# HI8596PSI.net
KiCad netlist of a schematic drawn in Altium Designer
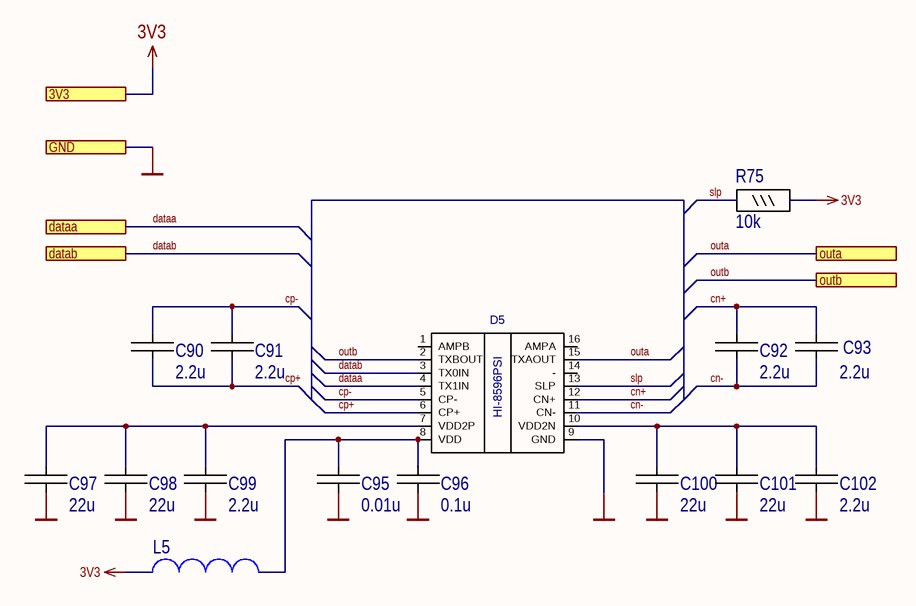
[diagram p0: HI8596PSI.SchDoc]

(export (version "E")
  (design (tool "Eeschema 10.0.6"))
  (components
    (comp (ref "C90")
      (value "2.2u")
      (footprint "C0603_IPC")
      (description "2.2µF ±10% 10V Ceramic Capacitor X7R 0603 (1608 Metric)")
      (fields (field (name "MPN") "CL10B225KP8NNNC") (field (name "TOLERANCE") "0,1"))
      (libsource (lib "DB_res_cap_ind") (part "C0603_GOST"))
    )
    (comp (ref "C91")
      (value "2.2u")
      (footprint "C0603_IPC")
      (description "2.2µF ±10% 10V Ceramic Capacitor X7R 0603 (1608 Metric)")
      (fields (field (name "MPN") "CL10B225KP8NNNC") (field (name "TOLERANCE") "0,1"))
      (libsource (lib "DB_res_cap_ind") (part "C0603_GOST"))
    )
    (comp (ref "C92")
      (value "2.2u")
      (footprint "C0603_IPC")
      (description "2.2µF ±10% 10V Ceramic Capacitor X7R 0603 (1608 Metric)")
      (fields (field (name "MPN") "CL10B225KP8NNNC") (field (name "TOLERANCE") "0,1"))
      (libsource (lib "DB_res_cap_ind") (part "C0603_GOST"))
    )
    (comp (ref "C93")
      (value "2.2u")
      (footprint "C0603_IPC")
      (description "2.2µF ±10% 10V Ceramic Capacitor X7R 0603 (1608 Metric)")
      (fields (field (name "MPN") "CL10B225KP8NNNC") (field (name "TOLERANCE") "0,1"))
      (libsource (lib "DB_res_cap_ind") (part "C0603_GOST"))
    )
    (comp (ref "C95")
      (value "0.01u")
      (footprint "C0603_IPC")
      (description "0.01uF ±10% 50V Ceramic Capacitor X7R 0603 (1608 Metric)")
      (fields (field (name "MPN") "CC0603KRX7R9BB103") (field (name "TOLERANCE") "0,1"))
      (libsource (lib "DB_res_cap_ind") (part "C0603_GOST"))
    )
    (comp (ref "C96")
      (value "0.1u")
      (footprint "C0603_IPC")
      (description "0.1uF ±10% 50V Ceramic Capacitor X7R 0603 (1608 Metric)")
      (fields (field (name "MPN") "CL10B104KB8NNND") (field (name "TOLERANCE") "0,1"))
      (libsource (lib "DB_res_cap_ind") (part "C0603_GOST"))
    )
    (comp (ref "C97")
      (value "22u")
      (footprint "C1206_IPC")
      (description "10µF ±10% 50V Ceramic Capacitor X5R 1206 (3216 Metric)")
      (fields
        (field (name "TOLERANCE") "0,2")
        (field (name "MANUFACTURER") "Murata Electronics North America")
      )
      (libsource (lib "DB_res_cap_ind") (part "C0603_GOST"))
    )
    (comp (ref "C98")
      (value "22u")
      (footprint "C1206_IPC")
      (description "10µF ±10% 50V Ceramic Capacitor X5R 1206 (3216 Metric)")
      (fields
        (field (name "TOLERANCE") "0,2")
        (field (name "MANUFACTURER") "Murata Electronics North America")
      )
      (libsource (lib "DB_res_cap_ind") (part "C0603_GOST"))
    )
    (comp (ref "C99")
      (value "2.2u")
      (footprint "C0603_IPC")
      (description "2.2µF ±10% 10V Ceramic Capacitor X7R 0603 (1608 Metric)")
      (fields (field (name "MPN") "CL10B225KP8NNNC") (field (name "TOLERANCE") "0,1"))
      (libsource (lib "DB_res_cap_ind") (part "C0603_GOST"))
    )
    (comp (ref "C100")
      (value "22u")
      (footprint "C1206_IPC")
      (description "10µF ±10% 50V Ceramic Capacitor X5R 1206 (3216 Metric)")
      (fields
        (field (name "TOLERANCE") "0,2")
        (field (name "MANUFACTURER") "Murata Electronics North America")
      )
      (libsource (lib "DB_res_cap_ind") (part "C0603_GOST"))
    )
    (comp (ref "C101")
      (value "22u")
      (footprint "C1206_IPC")
      (description "10µF ±10% 50V Ceramic Capacitor X5R 1206 (3216 Metric)")
      (fields
        (field (name "TOLERANCE") "0,2")
        (field (name "MANUFACTURER") "Murata Electronics North America")
      )
      (libsource (lib "DB_res_cap_ind") (part "C0603_GOST"))
    )
    (comp (ref "C102")
      (value "2.2u")
      (footprint "C0603_IPC")
      (description "2.2µF ±10% 10V Ceramic Capacitor X7R 0603 (1608 Metric)")
      (fields (field (name "MPN") "CL10B225KP8NNNC") (field (name "TOLERANCE") "0,1"))
      (libsource (lib "DB_res_cap_ind") (part "C0603_GOST"))
    )
    (comp (ref "D5")
      (value "HI-8596PSI")
      (footprint "soic16")
      (libsource (lib "EVAL_22_0B_rev_4_v2") (part "HI-8596PSI"))
    )
    (comp (ref "L5")
      (value "BLM21AG102SN1")
      (footprint "ind0805")
      (description "1 kOhms @ 100MHz 1 Ferrite Bead 0805 (2012 Metric) 500mA 280 mOhm")
      (fields
        (field (name "TOLERANCE") "±25%")
        (field (name "MANUFACTURER") "Murata Electronics North America")
      )
      (libsource (lib "DB_res_cap_ind") (part "INDUCTOR"))
    )
    (comp (ref "R75")
      (value "10k")
      (footprint "R0603")
      (description "10 kOhms ±5% 0.1W, 1/10W Chip Resistor 0603 (1608 Metric) Moisture Resistant Thick Film")
      (fields (field (name "MPN") "RC0603JR-0710kL") (field (name "TOLERANCE") "5%"))
      (libsource (lib "DB_res_cap_ind") (part "R0603"))
    )
  )
  (nets
    (net (code "1") (name "/cn+") (class "Default")
      (node (ref "C92") (pin "1") (pinfunction "1_1") (pintype "passive"))
      (node (ref "C93") (pin "1") (pinfunction "1_1") (pintype "passive"))
      (node (ref "D5") (pin "12") (pinfunction "CN+_12") (pintype "passive"))
    )
    (net (code "2") (name "/cn-") (class "Default")
      (node (ref "C92") (pin "2") (pinfunction "2_2") (pintype "passive"))
      (node (ref "C93") (pin "2") (pinfunction "2_2") (pintype "passive"))
      (node (ref "D5") (pin "11") (pinfunction "CN-_11") (pintype "passive"))
    )
    (net (code "3") (name "/cp+") (class "Default")
      (node (ref "C90") (pin "2") (pinfunction "2_2") (pintype "passive"))
      (node (ref "C91") (pin "2") (pinfunction "2_2") (pintype "passive"))
      (node (ref "D5") (pin "6") (pinfunction "CP+_6") (pintype "passive"))
    )
    (net (code "4") (name "/cp-") (class "Default")
      (node (ref "C90") (pin "1") (pinfunction "1_1") (pintype "passive"))
      (node (ref "C91") (pin "1") (pinfunction "1_1") (pintype "passive"))
      (node (ref "D5") (pin "5") (pinfunction "CP-_5") (pintype "passive"))
    )
    (net (code "5") (name "/dataa") (class "Default")
      (node (ref "D5") (pin "4") (pinfunction "TX1IN_4") (pintype "passive"))
    )
    (net (code "6") (name "/datab") (class "Default")
      (node (ref "D5") (pin "3") (pinfunction "TX0IN_3") (pintype "passive"))
    )
    (net (code "7") (name "/outa") (class "Default")
      (node (ref "D5") (pin "15") (pinfunction "TXAOUT_15") (pintype "passive"))
    )
    (net (code "8") (name "/outb") (class "Default")
      (node (ref "D5") (pin "2") (pinfunction "TXBOUT_2") (pintype "passive"))
    )
    (net (code "9") (name "/slp") (class "Default")
      (node (ref "D5") (pin "13") (pinfunction "SLP_13") (pintype "passive"))
      (node (ref "R75") (pin "1") (pinfunction "1_1") (pintype "passive"))
    )
    (net (code "10") (name "3V3") (class "Default")
      (node (ref "L5") (pin "1") (pinfunction "1_1") (pintype "passive"))
      (node (ref "R75") (pin "2") (pinfunction "2_2") (pintype "passive"))
    )
    (net (code "11") (name "GND") (class "Default")
      (node (ref "C100") (pin "2") (pinfunction "2_2") (pintype "passive"))
      (node (ref "C101") (pin "2") (pinfunction "2_2") (pintype "passive"))
      (node (ref "C102") (pin "2") (pinfunction "2_2") (pintype "passive"))
      (node (ref "C95") (pin "2") (pinfunction "2_2") (pintype "passive"))
      (node (ref "C96") (pin "2") (pinfunction "2_2") (pintype "passive"))
      (node (ref "C97") (pin "2") (pinfunction "2_2") (pintype "passive"))
      (node (ref "C98") (pin "2") (pinfunction "2_2") (pintype "passive"))
      (node (ref "C99") (pin "2") (pinfunction "2_2") (pintype "passive"))
      (node (ref "D5") (pin "9") (pinfunction "GND_9") (pintype "passive"))
    )
    (net (code "12") (name "Net-(D5-VDD)") (class "Default")
      (node (ref "C95") (pin "1") (pinfunction "1_1") (pintype "passive"))
      (node (ref "C96") (pin "1") (pinfunction "1_1") (pintype "passive"))
      (node (ref "D5") (pin "8") (pinfunction "VDD_8") (pintype "passive"))
      (node (ref "L5") (pin "2") (pinfunction "2_2") (pintype "passive"))
    )
    (net (code "13") (name "Net-(D5-VDD2N)") (class "Default")
      (node (ref "C100") (pin "1") (pinfunction "1_1") (pintype "passive"))
      (node (ref "C101") (pin "1") (pinfunction "1_1") (pintype "passive"))
      (node (ref "C102") (pin "1") (pinfunction "1_1") (pintype "passive"))
      (node (ref "D5") (pin "10") (pinfunction "VDD2N_10") (pintype "passive"))
    )
    (net (code "14") (name "Net-(D5-VDD2P)") (class "Default")
      (node (ref "C97") (pin "1") (pinfunction "1_1") (pintype "passive"))
      (node (ref "C98") (pin "1") (pinfunction "1_1") (pintype "passive"))
      (node (ref "C99") (pin "1") (pinfunction "1_1") (pintype "passive"))
      (node (ref "D5") (pin "7") (pinfunction "VDD2P_7") (pintype "passive"))
    )
    (net (code "15") (name "unconnected-(D5---Pad14)") (class "Default")
      (node (ref "D5") (pin "14") (pinfunction "-_14") (pintype "passive"))
    )
    (net (code "16") (name "unconnected-(D5-AMPA-Pad16)") (class "Default")
      (node (ref "D5") (pin "16") (pinfunction "AMPA_16") (pintype "passive"))
    )
    (net (code "17") (name "unconnected-(D5-AMPB-Pad1)") (class "Default")
      (node (ref "D5") (pin "1") (pinfunction "AMPB_1") (pintype "passive"))
    )
  )
)
